# TimeTracker_TestboardV1.net
KiCad netlist of a schematic drawn in EAGLE
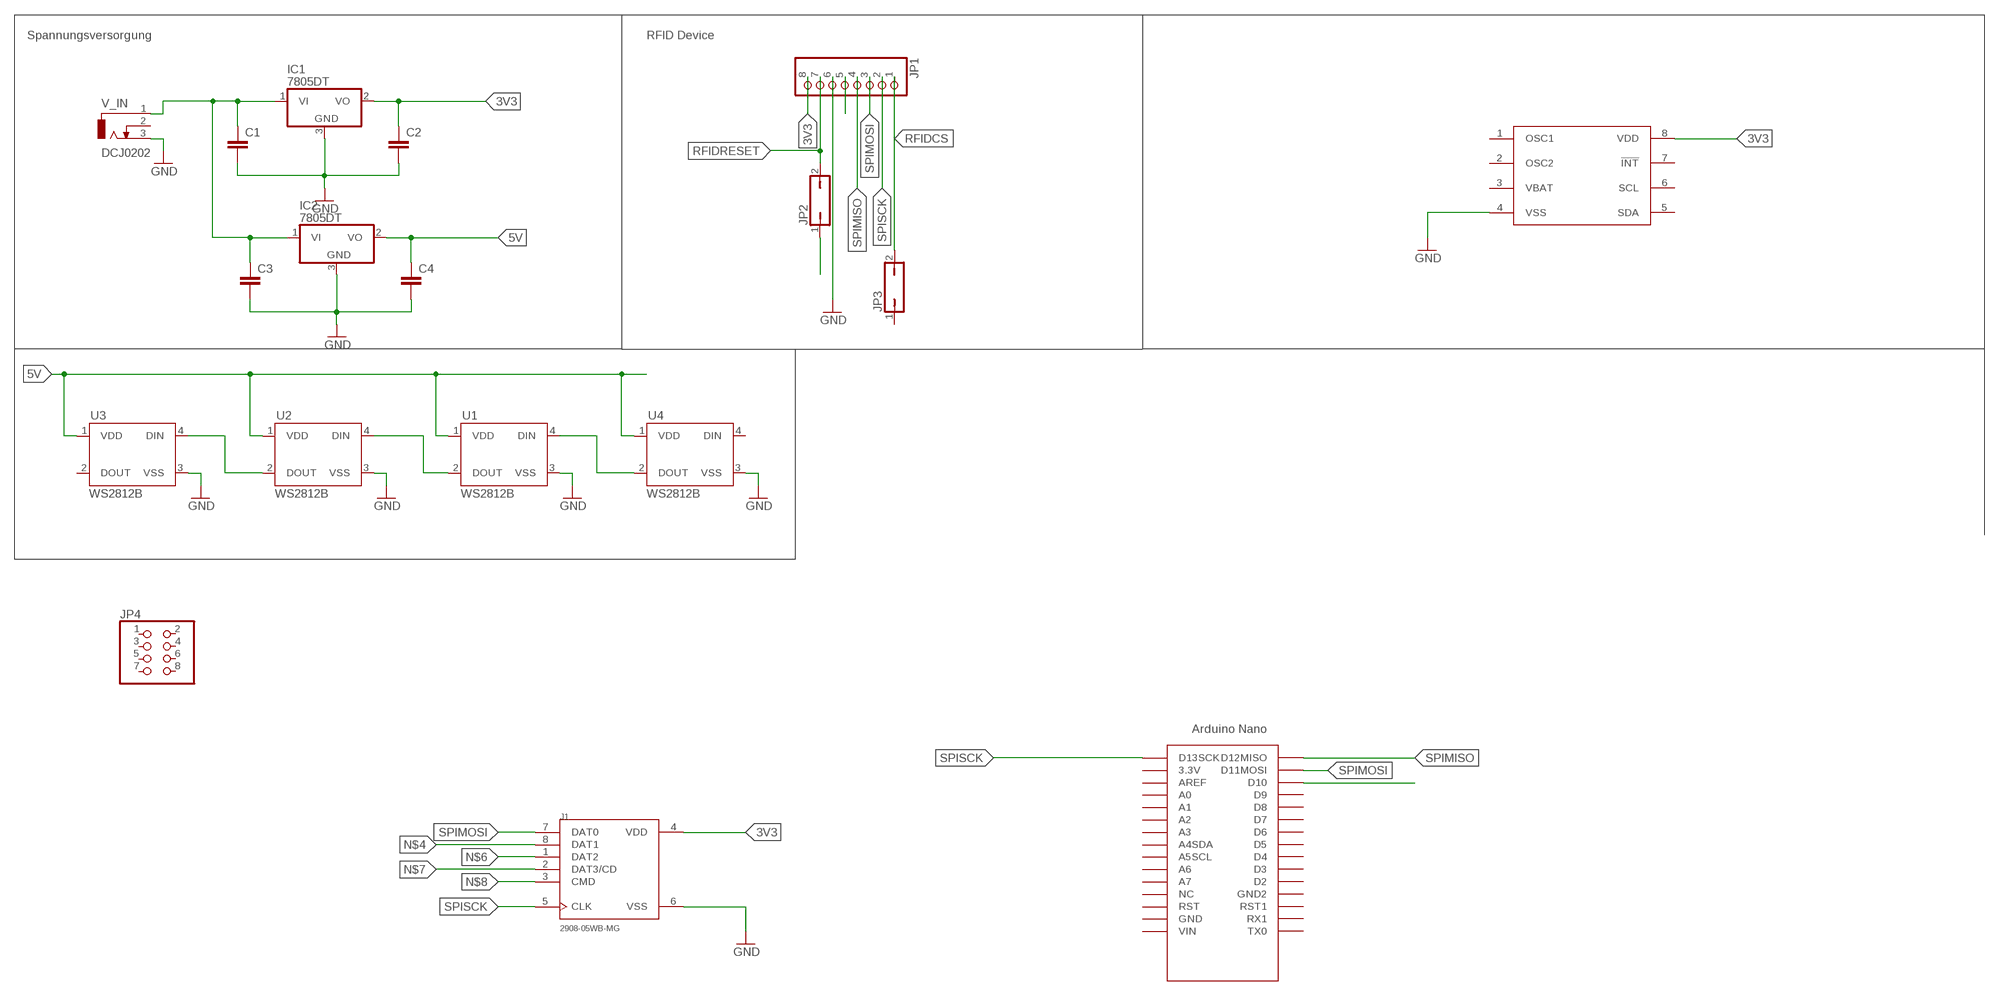
[diagram p0: schematic, sheet 1]

(export (version "E")
  (design (tool "Eeschema 10.0.6"))
  (components
    (comp (ref "C1")
      (value "C-EUC0805")
      (footprint "eagle-import:C0805")
      (libsource (lib "eagle-import") (part "C-EUC0805"))
    )
    (comp (ref "C2")
      (value "C-EUC0805")
      (footprint "eagle-import:C0805")
      (libsource (lib "eagle-import") (part "C-EUC0805"))
    )
    (comp (ref "C3")
      (value "C-EUC0805")
      (footprint "eagle-import:C0805")
      (libsource (lib "eagle-import") (part "C-EUC0805"))
    )
    (comp (ref "C4")
      (value "C-EUC0805")
      (footprint "eagle-import:C0805")
      (libsource (lib "eagle-import") (part "C-EUC0805"))
    )
    (comp (ref "IC1")
      (value "7805DT")
      (footprint "eagle-import:TO252")
      (libsource (lib "eagle-import") (part "78DT05"))
    )
    (comp (ref "IC2")
      (value "7805DT")
      (footprint "eagle-import:TO252")
      (libsource (lib "eagle-import") (part "78DT05"))
    )
    (comp (ref "J1")
      (value "2908-05WB-MG")
      (footprint "eagle-import:3M_2908-05WB-MG")
      (fields (field (name "MF") "3M"))
      (libsource (lib "eagle-import") (part "2908-05WB-MG"))
    )
    (comp (ref "JP1")
      (value "PINHD-1X8")
      (footprint "eagle-import:1X08")
      (libsource (lib "eagle-import") (part "PINHD-1X8"))
    )
    (comp (ref "JP2")
      (value "JP1Q")
      (footprint "eagle-import:JP1")
      (libsource (lib "eagle-import") (part "JP1Q"))
    )
    (comp (ref "JP3")
      (value "JP1Q")
      (footprint "eagle-import:JP1")
      (libsource (lib "eagle-import") (part "JP1Q"))
    )
    (comp (ref "JP4")
      (value "PINHD-2X4")
      (footprint "eagle-import:2X04")
      (libsource (lib "eagle-import") (part "PINHD-2X4"))
    )
    (comp (ref "U$1")
      (value "NANO")
      (footprint "eagle-import:NANO")
      (libsource (lib "eagle-import") (part "NANO"))
    )
    (comp (ref "U$2")
      (value "RTC")
      (footprint "eagle-import:SOP65P490X110-8N")
      (libsource (lib "eagle-import") (part "RTC"))
    )
    (comp (ref "U1")
      (value "WS2812B")
      (footprint "eagle-import:WS2812B")
      (libsource (lib "eagle-import") (part "WS2812B"))
    )
    (comp (ref "U2")
      (value "WS2812B")
      (footprint "eagle-import:WS2812B")
      (libsource (lib "eagle-import") (part "WS2812B"))
    )
    (comp (ref "U3")
      (value "WS2812B")
      (footprint "eagle-import:WS2812B")
      (libsource (lib "eagle-import") (part "WS2812B"))
    )
    (comp (ref "U4")
      (value "WS2812B")
      (footprint "eagle-import:WS2812B")
      (libsource (lib "eagle-import") (part "WS2812B"))
    )
    (comp (ref "V_IN")
      (value "DCJ0202")
      (footprint "eagle-import:DCJ0202")
      (libsource (lib "eagle-import") (part "DCJ0202"))
    )
  )
  (nets
    (net (code "1") (name "3V3") (class "Default")
      (node (ref "C2") (pin "1") (pinfunction "1_1") (pintype "passive"))
      (node (ref "IC1") (pin "2") (pinfunction "VO_2") (pintype "passive"))
      (node (ref "J1") (pin "4") (pinfunction "VDD_4") (pintype "power_in"))
      (node (ref "JP1") (pin "8") (pinfunction "8_8") (pintype "passive"))
      (node (ref "U$2") (pin "8") (pinfunction "VDD_8") (pintype "bidirectional"))
    )
    (net (code "2") (name "5V") (class "Default")
      (node (ref "C4") (pin "1") (pinfunction "1_1") (pintype "passive"))
      (node (ref "IC2") (pin "2") (pinfunction "VO_2") (pintype "passive"))
      (node (ref "U1") (pin "1") (pinfunction "VDD_1") (pintype "power_in"))
      (node (ref "U2") (pin "1") (pinfunction "VDD_1") (pintype "power_in"))
      (node (ref "U3") (pin "1") (pinfunction "VDD_1") (pintype "power_in"))
      (node (ref "U4") (pin "1") (pinfunction "VDD_1") (pintype "power_in"))
    )
    (net (code "3") (name "GND") (class "Default")
      (node (ref "C1") (pin "2") (pinfunction "2_2") (pintype "passive"))
      (node (ref "C2") (pin "2") (pinfunction "2_2") (pintype "passive"))
      (node (ref "C3") (pin "2") (pinfunction "2_2") (pintype "passive"))
      (node (ref "C4") (pin "2") (pinfunction "2_2") (pintype "passive"))
      (node (ref "IC1") (pin "3") (pinfunction "GND_3") (pintype "passive"))
      (node (ref "IC2") (pin "3") (pinfunction "GND_3") (pintype "passive"))
      (node (ref "J1") (pin "6") (pinfunction "VSS_6") (pintype "power_in"))
      (node (ref "JP1") (pin "6") (pinfunction "6_6") (pintype "passive"))
      (node (ref "U$2") (pin "4") (pinfunction "VSS_4") (pintype "bidirectional"))
      (node (ref "U1") (pin "3") (pinfunction "VSS_3") (pintype "power_in"))
      (node (ref "U2") (pin "3") (pinfunction "VSS_3") (pintype "power_in"))
      (node (ref "U3") (pin "3") (pinfunction "VSS_3") (pintype "power_in"))
      (node (ref "U4") (pin "3") (pinfunction "VSS_3") (pintype "power_in"))
      (node (ref "V_IN") (pin "3") (pinfunction "3_3") (pintype "passive"))
    )
    (net (code "4") (name "N$4") (class "Default")
      (node (ref "J1") (pin "8") (pinfunction "DAT1_8") (pintype "bidirectional"))
    )
    (net (code "5") (name "N$6") (class "Default")
      (node (ref "J1") (pin "1") (pinfunction "DAT2_1") (pintype "bidirectional"))
    )
    (net (code "6") (name "N$7") (class "Default")
      (node (ref "J1") (pin "2") (pinfunction "DAT3/CD_2") (pintype "bidirectional"))
    )
    (net (code "7") (name "N$8") (class "Default")
      (node (ref "J1") (pin "3") (pinfunction "CMD_3") (pintype "bidirectional"))
    )
    (net (code "8") (name "Net-(IC1-VI)") (class "Default")
      (node (ref "C1") (pin "1") (pinfunction "1_1") (pintype "passive"))
      (node (ref "C3") (pin "1") (pinfunction "1_1") (pintype "passive"))
      (node (ref "IC1") (pin "1") (pinfunction "VI_1") (pintype "input"))
      (node (ref "IC2") (pin "1") (pinfunction "VI_1") (pintype "input"))
      (node (ref "V_IN") (pin "1") (pinfunction "1_1") (pintype "passive"))
    )
    (net (code "9") (name "Net-(U1-DIN)") (class "Default")
      (node (ref "U1") (pin "4") (pinfunction "DIN_4") (pintype "input"))
      (node (ref "U4") (pin "2") (pinfunction "DOUT_2") (pintype "output"))
    )
    (net (code "10") (name "Net-(U1-DOUT)") (class "Default")
      (node (ref "U1") (pin "2") (pinfunction "DOUT_2") (pintype "output"))
      (node (ref "U2") (pin "4") (pinfunction "DIN_4") (pintype "input"))
    )
    (net (code "11") (name "Net-(U2-DOUT)") (class "Default")
      (node (ref "U2") (pin "2") (pinfunction "DOUT_2") (pintype "output"))
      (node (ref "U3") (pin "4") (pinfunction "DIN_4") (pintype "input"))
    )
    (net (code "12") (name "RFIDCS") (class "Default")
      (node (ref "JP1") (pin "1") (pinfunction "1_1") (pintype "passive"))
      (node (ref "JP3") (pin "2") (pinfunction "2_2") (pintype "passive"))
    )
    (net (code "13") (name "RFIDRESET") (class "Default")
      (node (ref "JP1") (pin "7") (pinfunction "7_7") (pintype "passive"))
      (node (ref "JP2") (pin "2") (pinfunction "2_2") (pintype "passive"))
    )
    (net (code "14") (name "SPIMISO") (class "Default")
      (node (ref "JP1") (pin "4") (pinfunction "4_4") (pintype "passive"))
      (node (ref "U$1") (pin "D12") (pinfunction "D12MISO_D12") (pintype "bidirectional"))
    )
    (net (code "15") (name "SPIMOSI") (class "Default")
      (node (ref "J1") (pin "7") (pinfunction "DAT0_7") (pintype "bidirectional"))
      (node (ref "JP1") (pin "3") (pinfunction "3_3") (pintype "passive"))
      (node (ref "U$1") (pin "D11") (pinfunction "D11MOSI_D11") (pintype "bidirectional"))
    )
    (net (code "16") (name "SPISCK") (class "Default")
      (node (ref "J1") (pin "5") (pinfunction "CLK_5") (pintype "bidirectional"))
      (node (ref "JP1") (pin "2") (pinfunction "2_2") (pintype "passive"))
      (node (ref "U$1") (pin "D13") (pinfunction "D13SCK_D13") (pintype "bidirectional"))
    )
    (net (code "17") (name "unconnected-(JP1-Pad5)") (class "Default")
      (node (ref "JP1") (pin "5") (pinfunction "5_5") (pintype "passive"))
    )
    (net (code "18") (name "unconnected-(JP2-Pad1)") (class "Default")
      (node (ref "JP2") (pin "1") (pinfunction "1_1") (pintype "passive"))
    )
    (net (code "19") (name "unconnected-(JP3-Pad1)") (class "Default")
      (node (ref "JP3") (pin "1") (pinfunction "1_1") (pintype "passive"))
    )
    (net (code "20") (name "unconnected-(JP4-Pad1)") (class "Default")
      (node (ref "JP4") (pin "1") (pinfunction "1_1") (pintype "passive"))
    )
    (net (code "21") (name "unconnected-(JP4-Pad2)") (class "Default")
      (node (ref "JP4") (pin "2") (pinfunction "2_2") (pintype "passive"))
    )
    (net (code "22") (name "unconnected-(JP4-Pad3)") (class "Default")
      (node (ref "JP4") (pin "3") (pinfunction "3_3") (pintype "passive"))
    )
    (net (code "23") (name "unconnected-(JP4-Pad4)") (class "Default")
      (node (ref "JP4") (pin "4") (pinfunction "4_4") (pintype "passive"))
    )
    (net (code "24") (name "unconnected-(JP4-Pad5)") (class "Default")
      (node (ref "JP4") (pin "5") (pinfunction "5_5") (pintype "passive"))
    )
    (net (code "25") (name "unconnected-(JP4-Pad6)") (class "Default")
      (node (ref "JP4") (pin "6") (pinfunction "6_6") (pintype "passive"))
    )
    (net (code "26") (name "unconnected-(JP4-Pad7)") (class "Default")
      (node (ref "JP4") (pin "7") (pinfunction "7_7") (pintype "passive"))
    )
    (net (code "27") (name "unconnected-(JP4-Pad8)") (class "Default")
      (node (ref "JP4") (pin "8") (pinfunction "8_8") (pintype "passive"))
    )
    (net (code "28") (name "unconnected-(U$1-A4SDA-PadA4)") (class "Default")
      (node (ref "U$1") (pin "A4") (pinfunction "A4SDA_A4") (pintype "bidirectional"))
    )
    (net (code "29") (name "unconnected-(U$1-A5SCL-PadA5)") (class "Default")
      (node (ref "U$1") (pin "A5") (pinfunction "A5SCL_A5") (pintype "bidirectional"))
    )
    (net (code "30") (name "unconnected-(U$1-GND2-PadGND1)") (class "Default")
      (node (ref "U$1") (pin "GND1") (pinfunction "GND2_GND1") (pintype "bidirectional"))
    )
    (net (code "31") (name "unconnected-(U$1-NC-Pad5V)") (class "Default")
      (node (ref "U$1") (pin "5V") (pinfunction "NC_5V") (pintype "bidirectional"))
    )
    (net (code "32") (name "unconnected-(U$1-Pad3.3V)") (class "Default")
      (node (ref "U$1") (pin "3.3V") (pinfunction "3.3V_3.3V") (pintype "bidirectional"))
    )
    (net (code "33") (name "unconnected-(U$1-PadA0)") (class "Default")
      (node (ref "U$1") (pin "A0") (pinfunction "A0_A0") (pintype "bidirectional"))
    )
    (net (code "34") (name "unconnected-(U$1-PadA1)") (class "Default")
      (node (ref "U$1") (pin "A1") (pinfunction "A1_A1") (pintype "bidirectional"))
    )
    (net (code "35") (name "unconnected-(U$1-PadA2)") (class "Default")
      (node (ref "U$1") (pin "A2") (pinfunction "A2_A2") (pintype "bidirectional"))
    )
    (net (code "36") (name "unconnected-(U$1-PadA3)") (class "Default")
      (node (ref "U$1") (pin "A3") (pinfunction "A3_A3") (pintype "bidirectional"))
    )
    (net (code "37") (name "unconnected-(U$1-PadA6)") (class "Default")
      (node (ref "U$1") (pin "A6") (pinfunction "A6_A6") (pintype "bidirectional"))
    )
    (net (code "38") (name "unconnected-(U$1-PadA7)") (class "Default")
      (node (ref "U$1") (pin "A7") (pinfunction "A7_A7") (pintype "bidirectional"))
    )
    (net (code "39") (name "unconnected-(U$1-PadAREF)") (class "Default")
      (node (ref "U$1") (pin "AREF") (pinfunction "AREF_AREF") (pintype "bidirectional"))
    )
    (net (code "40") (name "unconnected-(U$1-PadD2)") (class "Default")
      (node (ref "U$1") (pin "D2") (pinfunction "D2_D2") (pintype "bidirectional"))
    )
    (net (code "41") (name "unconnected-(U$1-PadD3)") (class "Default")
      (node (ref "U$1") (pin "D3") (pinfunction "D3_D3") (pintype "bidirectional"))
    )
    (net (code "42") (name "unconnected-(U$1-PadD4)") (class "Default")
      (node (ref "U$1") (pin "D4") (pinfunction "D4_D4") (pintype "bidirectional"))
    )
    (net (code "43") (name "unconnected-(U$1-PadD5)") (class "Default")
      (node (ref "U$1") (pin "D5") (pinfunction "D5_D5") (pintype "bidirectional"))
    )
    (net (code "44") (name "unconnected-(U$1-PadD6)") (class "Default")
      (node (ref "U$1") (pin "D6") (pinfunction "D6_D6") (pintype "bidirectional"))
    )
    (net (code "45") (name "unconnected-(U$1-PadD7)") (class "Default")
      (node (ref "U$1") (pin "D7") (pinfunction "D7_D7") (pintype "bidirectional"))
    )
    (net (code "46") (name "unconnected-(U$1-PadD8)") (class "Default")
      (node (ref "U$1") (pin "D8") (pinfunction "D8_D8") (pintype "bidirectional"))
    )
    (net (code "47") (name "unconnected-(U$1-PadD9)") (class "Default")
      (node (ref "U$1") (pin "D9") (pinfunction "D9_D9") (pintype "bidirectional"))
    )
    (net (code "48") (name "unconnected-(U$1-PadD10)") (class "Default")
      (node (ref "U$1") (pin "D10") (pinfunction "D10_D10") (pintype "bidirectional"))
    )
    (net (code "49") (name "unconnected-(U$1-PadGND)") (class "Default")
      (node (ref "U$1") (pin "GND") (pinfunction "GND_GND") (pintype "bidirectional"))
    )
    (net (code "50") (name "unconnected-(U$1-PadRST)") (class "Default")
      (node (ref "U$1") (pin "RST") (pinfunction "RST_RST") (pintype "bidirectional"))
    )
    (net (code "51") (name "unconnected-(U$1-PadRST1)") (class "Default")
      (node (ref "U$1") (pin "RST1") (pinfunction "RST1_RST1") (pintype "bidirectional"))
    )
    (net (code "52") (name "unconnected-(U$1-PadRX1)") (class "Default")
      (node (ref "U$1") (pin "RX1") (pinfunction "RX1_RX1") (pintype "bidirectional"))
    )
    (net (code "53") (name "unconnected-(U$1-PadTX0)") (class "Default")
      (node (ref "U$1") (pin "TX0") (pinfunction "TX0_TX0") (pintype "bidirectional"))
    )
    (net (code "54") (name "unconnected-(U$1-VIN-PadRAW)") (class "Default")
      (node (ref "U$1") (pin "RAW") (pinfunction "VIN_RAW") (pintype "bidirectional"))
    )
    (net (code "55") (name "unconnected-(U$2-OSC1-Pad1)") (class "Default")
      (node (ref "U$2") (pin "1") (pinfunction "OSC1_1") (pintype "bidirectional"))
    )
    (net (code "56") (name "unconnected-(U$2-OSC2-Pad2)") (class "Default")
      (node (ref "U$2") (pin "2") (pinfunction "OSC2_2") (pintype "bidirectional"))
    )
    (net (code "57") (name "unconnected-(U$2-SCL-Pad6)") (class "Default")
      (node (ref "U$2") (pin "6") (pinfunction "SCL_6") (pintype "bidirectional"))
    )
    (net (code "58") (name "unconnected-(U$2-SDA-Pad5)") (class "Default")
      (node (ref "U$2") (pin "5") (pinfunction "SDA_5") (pintype "bidirectional"))
    )
    (net (code "59") (name "unconnected-(U$2-VBAT-Pad3)") (class "Default")
      (node (ref "U$2") (pin "3") (pinfunction "VBAT_3") (pintype "bidirectional"))
    )
    (net (code "60") (name "unconnected-(U$2-~{INT}-Pad7)") (class "Default")
      (node (ref "U$2") (pin "7") (pinfunction "~{INT}_7") (pintype "bidirectional"))
    )
    (net (code "61") (name "unconnected-(U3-DOUT-Pad2)") (class "Default")
      (node (ref "U3") (pin "2") (pinfunction "DOUT_2") (pintype "output"))
    )
    (net (code "62") (name "unconnected-(U4-DIN-Pad4)") (class "Default")
      (node (ref "U4") (pin "4") (pinfunction "DIN_4") (pintype "input"))
    )
    (net (code "63") (name "unconnected-(V_IN-Pad2)") (class "Default")
      (node (ref "V_IN") (pin "2") (pinfunction "2_2") (pintype "passive"))
    )
  )
)
